# AMS_Enerdel_Adapter_rev8.net
KiCad netlist of a schematic drawn in EAGLE
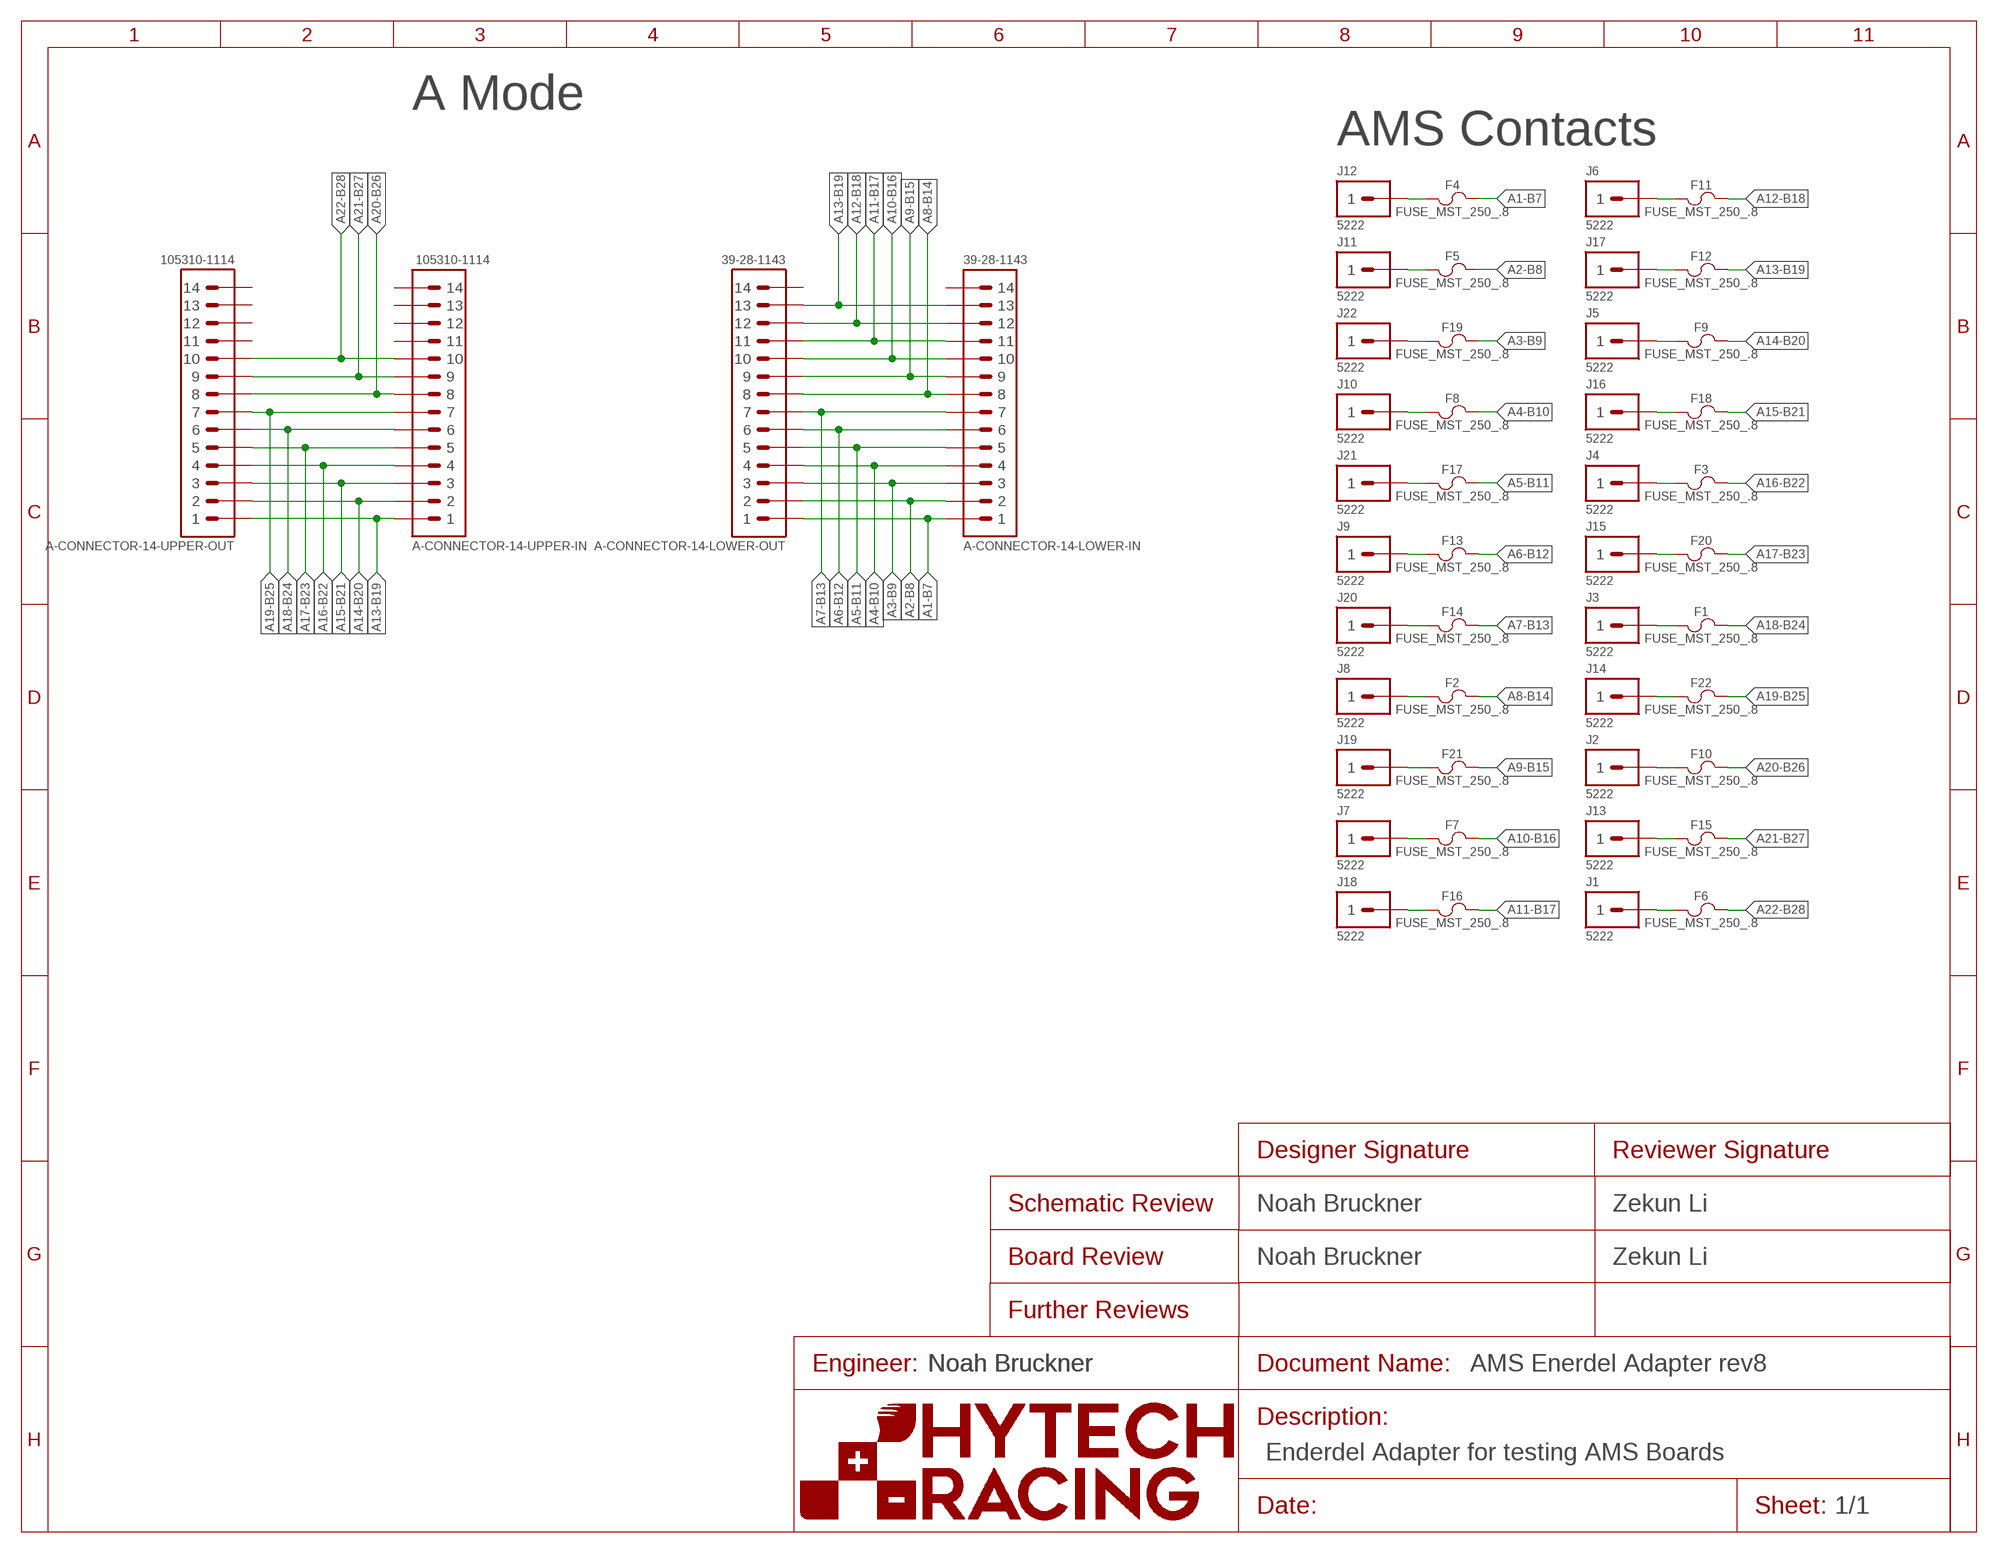
[diagram p0: schematic, sheet 1]

(export (version "E")
  (design (tool "Eeschema 10.0.6"))
  (components
    (comp (ref "A-CONNECTOR-14-LOWER-IN")
      (value "CONNECTOR-14_MINIFIT_")
      (footprint "eagle-import:MOLEX_MINIFIT_PTH_14")
      (fields (field (name "MPN") "39-28-1143"))
      (libsource (lib "eagle-import") (part "CONNECTOR-14_?_MINIFIT"))
    )
    (comp (ref "A-CONNECTOR-14-LOWER-OUT")
      (value "CONNECTOR-14_MINIFIT_")
      (footprint "eagle-import:MOLEX_MINIFIT_PTH_14")
      (fields (field (name "MPN") "39-28-1143"))
      (libsource (lib "eagle-import") (part "CONNECTOR-14_?_MINIFIT"))
    )
    (comp (ref "A-CONNECTOR-14-UPPER-IN")
      (value "CONNECTOR-14_NANOFIT_")
      (footprint "eagle-import:MOLEX_NANOFIT_PTH_14")
      (fields (field (name "MPN") " 105310-1114"))
      (libsource (lib "eagle-import") (part "CONNECTOR-14_?_NANOFIT"))
    )
    (comp (ref "A-CONNECTOR-14-UPPER-OUT")
      (value "CONNECTOR-14_NANOFIT_")
      (footprint "eagle-import:MOLEX_NANOFIT_PTH_14")
      (fields (field (name "MPN") "105310-1114"))
      (libsource (lib "eagle-import") (part "CONNECTOR-14_?_NANOFIT"))
    )
    (comp (ref "F1")
      (value "FUSE_MST_250_.8")
      (footprint "eagle-import:MST_250")
      (fields
        (field (name "MANUFACTURER") "Schurter Inc.")
        (field (name "MPN") "0034.6614")
        (field (name "VOLTAGE") "63V")
      )
      (libsource (lib "eagle-import") (part "FUSE_?_MST_250.8"))
    )
    (comp (ref "F2")
      (value "FUSE_MST_250_.8")
      (footprint "eagle-import:MST_250")
      (fields
        (field (name "MANUFACTURER") "Schurter Inc.")
        (field (name "MPN") "0034.6614")
        (field (name "VOLTAGE") "63V")
      )
      (libsource (lib "eagle-import") (part "FUSE_?_MST_250.8"))
    )
    (comp (ref "F3")
      (value "FUSE_MST_250_.8")
      (footprint "eagle-import:MST_250")
      (fields
        (field (name "MANUFACTURER") "Schurter Inc.")
        (field (name "MPN") "0034.6614")
        (field (name "VOLTAGE") "63V")
      )
      (libsource (lib "eagle-import") (part "FUSE_?_MST_250.8"))
    )
    (comp (ref "F4")
      (value "FUSE_MST_250_.8")
      (footprint "eagle-import:MST_250")
      (fields
        (field (name "MANUFACTURER") "Schurter Inc.")
        (field (name "MPN") "0034.6614")
        (field (name "VOLTAGE") "63V")
      )
      (libsource (lib "eagle-import") (part "FUSE_?_MST_250.8"))
    )
    (comp (ref "F5")
      (value "FUSE_MST_250_.8")
      (footprint "eagle-import:MST_250")
      (fields
        (field (name "MANUFACTURER") "Schurter Inc.")
        (field (name "MPN") "0034.6614")
        (field (name "VOLTAGE") "63V")
      )
      (libsource (lib "eagle-import") (part "FUSE_?_MST_250.8"))
    )
    (comp (ref "F6")
      (value "FUSE_MST_250_.8")
      (footprint "eagle-import:MST_250")
      (fields
        (field (name "MANUFACTURER") "Schurter Inc.")
        (field (name "MPN") "0034.6614")
        (field (name "VOLTAGE") "63V")
      )
      (libsource (lib "eagle-import") (part "FUSE_?_MST_250.8"))
    )
    (comp (ref "F7")
      (value "FUSE_MST_250_.8")
      (footprint "eagle-import:MST_250")
      (fields
        (field (name "MANUFACTURER") "Schurter Inc.")
        (field (name "MPN") "0034.6614")
        (field (name "VOLTAGE") "63V")
      )
      (libsource (lib "eagle-import") (part "FUSE_?_MST_250.8"))
    )
    (comp (ref "F8")
      (value "FUSE_MST_250_.8")
      (footprint "eagle-import:MST_250")
      (fields
        (field (name "MANUFACTURER") "Schurter Inc.")
        (field (name "MPN") "0034.6614")
        (field (name "VOLTAGE") "63V")
      )
      (libsource (lib "eagle-import") (part "FUSE_?_MST_250.8"))
    )
    (comp (ref "F9")
      (value "FUSE_MST_250_.8")
      (footprint "eagle-import:MST_250")
      (fields
        (field (name "MANUFACTURER") "Schurter Inc.")
        (field (name "MPN") "0034.6614")
        (field (name "VOLTAGE") "63V")
      )
      (libsource (lib "eagle-import") (part "FUSE_?_MST_250.8"))
    )
    (comp (ref "F10")
      (value "FUSE_MST_250_.8")
      (footprint "eagle-import:MST_250")
      (fields
        (field (name "MANUFACTURER") "Schurter Inc.")
        (field (name "MPN") "0034.6614")
        (field (name "VOLTAGE") "63V")
      )
      (libsource (lib "eagle-import") (part "FUSE_?_MST_250.8"))
    )
    (comp (ref "F11")
      (value "FUSE_MST_250_.8")
      (footprint "eagle-import:MST_250")
      (fields
        (field (name "MANUFACTURER") "Schurter Inc.")
        (field (name "MPN") "0034.6614")
        (field (name "VOLTAGE") "63V")
      )
      (libsource (lib "eagle-import") (part "FUSE_?_MST_250.8"))
    )
    (comp (ref "F12")
      (value "FUSE_MST_250_.8")
      (footprint "eagle-import:MST_250")
      (fields
        (field (name "MANUFACTURER") "Schurter Inc.")
        (field (name "MPN") "0034.6614")
        (field (name "VOLTAGE") "63V")
      )
      (libsource (lib "eagle-import") (part "FUSE_?_MST_250.8"))
    )
    (comp (ref "F13")
      (value "FUSE_MST_250_.8")
      (footprint "eagle-import:MST_250")
      (fields
        (field (name "MANUFACTURER") "Schurter Inc.")
        (field (name "MPN") "0034.6614")
        (field (name "VOLTAGE") "63V")
      )
      (libsource (lib "eagle-import") (part "FUSE_?_MST_250.8"))
    )
    (comp (ref "F14")
      (value "FUSE_MST_250_.8")
      (footprint "eagle-import:MST_250")
      (fields
        (field (name "MANUFACTURER") "Schurter Inc.")
        (field (name "MPN") "0034.6614")
        (field (name "VOLTAGE") "63V")
      )
      (libsource (lib "eagle-import") (part "FUSE_?_MST_250.8"))
    )
    (comp (ref "F15")
      (value "FUSE_MST_250_.8")
      (footprint "eagle-import:MST_250")
      (fields
        (field (name "MANUFACTURER") "Schurter Inc.")
        (field (name "MPN") "0034.6614")
        (field (name "VOLTAGE") "63V")
      )
      (libsource (lib "eagle-import") (part "FUSE_?_MST_250.8"))
    )
    (comp (ref "F16")
      (value "FUSE_MST_250_.8")
      (footprint "eagle-import:MST_250")
      (fields
        (field (name "MANUFACTURER") "Schurter Inc.")
        (field (name "MPN") "0034.6614")
        (field (name "VOLTAGE") "63V")
      )
      (libsource (lib "eagle-import") (part "FUSE_?_MST_250.8"))
    )
    (comp (ref "F17")
      (value "FUSE_MST_250_.8")
      (footprint "eagle-import:MST_250")
      (fields
        (field (name "MANUFACTURER") "Schurter Inc.")
        (field (name "MPN") "0034.6614")
        (field (name "VOLTAGE") "63V")
      )
      (libsource (lib "eagle-import") (part "FUSE_?_MST_250.8"))
    )
    (comp (ref "F18")
      (value "FUSE_MST_250_.8")
      (footprint "eagle-import:MST_250")
      (fields
        (field (name "MANUFACTURER") "Schurter Inc.")
        (field (name "MPN") "0034.6614")
        (field (name "VOLTAGE") "63V")
      )
      (libsource (lib "eagle-import") (part "FUSE_?_MST_250.8"))
    )
    (comp (ref "F19")
      (value "FUSE_MST_250_.8")
      (footprint "eagle-import:MST_250")
      (fields
        (field (name "MANUFACTURER") "Schurter Inc.")
        (field (name "MPN") "0034.6614")
        (field (name "VOLTAGE") "63V")
      )
      (libsource (lib "eagle-import") (part "FUSE_?_MST_250.8"))
    )
    (comp (ref "F20")
      (value "FUSE_MST_250_.8")
      (footprint "eagle-import:MST_250")
      (fields
        (field (name "MANUFACTURER") "Schurter Inc.")
        (field (name "MPN") "0034.6614")
        (field (name "VOLTAGE") "63V")
      )
      (libsource (lib "eagle-import") (part "FUSE_?_MST_250.8"))
    )
    (comp (ref "F21")
      (value "FUSE_MST_250_.8")
      (footprint "eagle-import:MST_250")
      (fields
        (field (name "MANUFACTURER") "Schurter Inc.")
        (field (name "MPN") "0034.6614")
        (field (name "VOLTAGE") "63V")
      )
      (libsource (lib "eagle-import") (part "FUSE_?_MST_250.8"))
    )
    (comp (ref "F22")
      (value "FUSE_MST_250_.8")
      (footprint "eagle-import:MST_250")
      (fields
        (field (name "MANUFACTURER") "Schurter Inc.")
        (field (name "MPN") "0034.6614")
        (field (name "VOLTAGE") "63V")
      )
      (libsource (lib "eagle-import") (part "FUSE_?_MST_250.8"))
    )
    (comp (ref "J1")
      (value "CONNECTOR-1_5222_")
      (footprint "eagle-import:5222")
      (fields (field (name "MPN") "5222") (field (name "MANUFACTURER") "Keystone Electronics"))
      (libsource (lib "eagle-import") (part "CONNECTOR-1_?_5222"))
    )
    (comp (ref "J2")
      (value "CONNECTOR-1_5222_")
      (footprint "eagle-import:5222")
      (fields (field (name "MPN") "5222") (field (name "MANUFACTURER") "Keystone Electronics"))
      (libsource (lib "eagle-import") (part "CONNECTOR-1_?_5222"))
    )
    (comp (ref "J3")
      (value "CONNECTOR-1_5222_")
      (footprint "eagle-import:5222")
      (fields (field (name "MPN") "5222") (field (name "MANUFACTURER") "Keystone Electronics"))
      (libsource (lib "eagle-import") (part "CONNECTOR-1_?_5222"))
    )
    (comp (ref "J4")
      (value "CONNECTOR-1_5222_")
      (footprint "eagle-import:5222")
      (fields (field (name "MPN") "5222") (field (name "MANUFACTURER") "Keystone Electronics"))
      (libsource (lib "eagle-import") (part "CONNECTOR-1_?_5222"))
    )
    (comp (ref "J5")
      (value "CONNECTOR-1_5222_")
      (footprint "eagle-import:5222")
      (fields (field (name "MPN") "5222") (field (name "MANUFACTURER") "Keystone Electronics"))
      (libsource (lib "eagle-import") (part "CONNECTOR-1_?_5222"))
    )
    (comp (ref "J6")
      (value "CONNECTOR-1_5222_")
      (footprint "eagle-import:5222")
      (fields (field (name "MPN") "5222") (field (name "MANUFACTURER") "Keystone Electronics"))
      (libsource (lib "eagle-import") (part "CONNECTOR-1_?_5222"))
    )
    (comp (ref "J7")
      (value "CONNECTOR-1_5222_")
      (footprint "eagle-import:5222")
      (fields (field (name "MPN") "5222") (field (name "MANUFACTURER") "Keystone Electronics"))
      (libsource (lib "eagle-import") (part "CONNECTOR-1_?_5222"))
    )
    (comp (ref "J8")
      (value "CONNECTOR-1_5222_")
      (footprint "eagle-import:5222")
      (fields (field (name "MPN") "5222") (field (name "MANUFACTURER") "Keystone Electronics"))
      (libsource (lib "eagle-import") (part "CONNECTOR-1_?_5222"))
    )
    (comp (ref "J9")
      (value "CONNECTOR-1_5222_")
      (footprint "eagle-import:5222")
      (fields (field (name "MPN") "5222") (field (name "MANUFACTURER") "Keystone Electronics"))
      (libsource (lib "eagle-import") (part "CONNECTOR-1_?_5222"))
    )
    (comp (ref "J10")
      (value "CONNECTOR-1_5222_")
      (footprint "eagle-import:5222")
      (fields (field (name "MPN") "5222") (field (name "MANUFACTURER") "Keystone Electronics"))
      (libsource (lib "eagle-import") (part "CONNECTOR-1_?_5222"))
    )
    (comp (ref "J11")
      (value "CONNECTOR-1_5222_")
      (footprint "eagle-import:5222")
      (fields (field (name "MPN") "5222") (field (name "MANUFACTURER") "Keystone Electronics"))
      (libsource (lib "eagle-import") (part "CONNECTOR-1_?_5222"))
    )
    (comp (ref "J12")
      (value "CONNECTOR-1_5222_")
      (footprint "eagle-import:5222")
      (fields (field (name "MPN") "5222") (field (name "MANUFACTURER") "Keystone Electronics"))
      (libsource (lib "eagle-import") (part "CONNECTOR-1_?_5222"))
    )
    (comp (ref "J13")
      (value "CONNECTOR-1_5222_")
      (footprint "eagle-import:5222")
      (fields (field (name "MPN") "5222") (field (name "MANUFACTURER") "Keystone Electronics"))
      (libsource (lib "eagle-import") (part "CONNECTOR-1_?_5222"))
    )
    (comp (ref "J14")
      (value "CONNECTOR-1_5222_")
      (footprint "eagle-import:5222")
      (fields (field (name "MPN") "5222") (field (name "MANUFACTURER") "Keystone Electronics"))
      (libsource (lib "eagle-import") (part "CONNECTOR-1_?_5222"))
    )
    (comp (ref "J15")
      (value "CONNECTOR-1_5222_")
      (footprint "eagle-import:5222")
      (fields (field (name "MPN") "5222") (field (name "MANUFACTURER") "Keystone Electronics"))
      (libsource (lib "eagle-import") (part "CONNECTOR-1_?_5222"))
    )
    (comp (ref "J16")
      (value "CONNECTOR-1_5222_")
      (footprint "eagle-import:5222")
      (fields (field (name "MPN") "5222") (field (name "MANUFACTURER") "Keystone Electronics"))
      (libsource (lib "eagle-import") (part "CONNECTOR-1_?_5222"))
    )
    (comp (ref "J17")
      (value "CONNECTOR-1_5222_")
      (footprint "eagle-import:5222")
      (fields (field (name "MPN") "5222") (field (name "MANUFACTURER") "Keystone Electronics"))
      (libsource (lib "eagle-import") (part "CONNECTOR-1_?_5222"))
    )
    (comp (ref "J18")
      (value "CONNECTOR-1_5222_")
      (footprint "eagle-import:5222")
      (fields (field (name "MPN") "5222") (field (name "MANUFACTURER") "Keystone Electronics"))
      (libsource (lib "eagle-import") (part "CONNECTOR-1_?_5222"))
    )
    (comp (ref "J19")
      (value "CONNECTOR-1_5222_")
      (footprint "eagle-import:5222")
      (fields (field (name "MPN") "5222") (field (name "MANUFACTURER") "Keystone Electronics"))
      (libsource (lib "eagle-import") (part "CONNECTOR-1_?_5222"))
    )
    (comp (ref "J20")
      (value "CONNECTOR-1_5222_")
      (footprint "eagle-import:5222")
      (fields (field (name "MPN") "5222") (field (name "MANUFACTURER") "Keystone Electronics"))
      (libsource (lib "eagle-import") (part "CONNECTOR-1_?_5222"))
    )
    (comp (ref "J21")
      (value "CONNECTOR-1_5222_")
      (footprint "eagle-import:5222")
      (fields (field (name "MPN") "5222") (field (name "MANUFACTURER") "Keystone Electronics"))
      (libsource (lib "eagle-import") (part "CONNECTOR-1_?_5222"))
    )
    (comp (ref "J22")
      (value "CONNECTOR-1_5222_")
      (footprint "eagle-import:5222")
      (fields (field (name "MPN") "5222") (field (name "MANUFACTURER") "Keystone Electronics"))
      (libsource (lib "eagle-import") (part "CONNECTOR-1_?_5222"))
    )
  )
  (nets
    (net (code "1") (name "A1-B7") (class "Default")
      (node (ref "A-CONNECTOR-14-LOWER-IN") (pin "1") (pinfunction "1_1") (pintype "passive"))
      (node (ref "A-CONNECTOR-14-LOWER-OUT") (pin "1") (pinfunction "1_1") (pintype "passive"))
      (node (ref "F4") (pin "2") (pinfunction "2_2") (pintype "passive"))
    )
    (net (code "2") (name "A2-B8") (class "Default")
      (node (ref "A-CONNECTOR-14-LOWER-IN") (pin "2") (pinfunction "2_2") (pintype "passive"))
      (node (ref "A-CONNECTOR-14-LOWER-OUT") (pin "2") (pinfunction "2_2") (pintype "passive"))
      (node (ref "F5") (pin "2") (pinfunction "2_2") (pintype "passive"))
    )
    (net (code "3") (name "A3-B9") (class "Default")
      (node (ref "A-CONNECTOR-14-LOWER-IN") (pin "3") (pinfunction "3_3") (pintype "passive"))
      (node (ref "A-CONNECTOR-14-LOWER-OUT") (pin "3") (pinfunction "3_3") (pintype "passive"))
      (node (ref "F19") (pin "2") (pinfunction "2_2") (pintype "passive"))
    )
    (net (code "4") (name "A4-B10") (class "Default")
      (node (ref "A-CONNECTOR-14-LOWER-IN") (pin "4") (pinfunction "4_4") (pintype "passive"))
      (node (ref "A-CONNECTOR-14-LOWER-OUT") (pin "4") (pinfunction "4_4") (pintype "passive"))
      (node (ref "F8") (pin "2") (pinfunction "2_2") (pintype "passive"))
    )
    (net (code "5") (name "A5-B11") (class "Default")
      (node (ref "A-CONNECTOR-14-LOWER-IN") (pin "5") (pinfunction "5_5") (pintype "passive"))
      (node (ref "A-CONNECTOR-14-LOWER-OUT") (pin "5") (pinfunction "5_5") (pintype "passive"))
      (node (ref "F17") (pin "2") (pinfunction "2_2") (pintype "passive"))
    )
    (net (code "6") (name "A6-B12") (class "Default")
      (node (ref "A-CONNECTOR-14-LOWER-IN") (pin "6") (pinfunction "6_6") (pintype "passive"))
      (node (ref "A-CONNECTOR-14-LOWER-OUT") (pin "6") (pinfunction "6_6") (pintype "passive"))
      (node (ref "F13") (pin "2") (pinfunction "2_2") (pintype "passive"))
    )
    (net (code "7") (name "A7-B13") (class "Default")
      (node (ref "A-CONNECTOR-14-LOWER-IN") (pin "7") (pinfunction "7_7") (pintype "passive"))
      (node (ref "A-CONNECTOR-14-LOWER-OUT") (pin "7") (pinfunction "7_7") (pintype "passive"))
      (node (ref "F14") (pin "2") (pinfunction "2_2") (pintype "passive"))
    )
    (net (code "8") (name "A8-B14") (class "Default")
      (node (ref "A-CONNECTOR-14-LOWER-IN") (pin "8") (pinfunction "8_8") (pintype "passive"))
      (node (ref "A-CONNECTOR-14-LOWER-OUT") (pin "8") (pinfunction "8_8") (pintype "passive"))
      (node (ref "F2") (pin "2") (pinfunction "2_2") (pintype "passive"))
    )
    (net (code "9") (name "A9-B15") (class "Default")
      (node (ref "A-CONNECTOR-14-LOWER-IN") (pin "9") (pinfunction "9_9") (pintype "passive"))
      (node (ref "A-CONNECTOR-14-LOWER-OUT") (pin "9") (pinfunction "9_9") (pintype "passive"))
      (node (ref "F21") (pin "2") (pinfunction "2_2") (pintype "passive"))
    )
    (net (code "10") (name "A10-B16") (class "Default")
      (node (ref "A-CONNECTOR-14-LOWER-IN") (pin "10") (pinfunction "10_10") (pintype "passive"))
      (node (ref "A-CONNECTOR-14-LOWER-OUT") (pin "10") (pinfunction "10_10") (pintype "passive"))
      (node (ref "F7") (pin "2") (pinfunction "2_2") (pintype "passive"))
    )
    (net (code "11") (name "A11-B17") (class "Default")
      (node (ref "A-CONNECTOR-14-LOWER-IN") (pin "11") (pinfunction "11_11") (pintype "passive"))
      (node (ref "A-CONNECTOR-14-LOWER-OUT") (pin "11") (pinfunction "11_11") (pintype "passive"))
      (node (ref "F16") (pin "2") (pinfunction "2_2") (pintype "passive"))
    )
    (net (code "12") (name "A12-B18") (class "Default")
      (node (ref "A-CONNECTOR-14-LOWER-IN") (pin "12") (pinfunction "12_12") (pintype "passive"))
      (node (ref "A-CONNECTOR-14-LOWER-OUT") (pin "12") (pinfunction "12_12") (pintype "passive"))
      (node (ref "F11") (pin "2") (pinfunction "2_2") (pintype "passive"))
    )
    (net (code "13") (name "A13-B19") (class "Default")
      (node (ref "A-CONNECTOR-14-LOWER-IN") (pin "13") (pinfunction "13_13") (pintype "passive"))
      (node (ref "A-CONNECTOR-14-LOWER-OUT") (pin "13") (pinfunction "13_13") (pintype "passive"))
      (node (ref "A-CONNECTOR-14-UPPER-IN") (pin "1") (pinfunction "1_1") (pintype "passive"))
      (node (ref "A-CONNECTOR-14-UPPER-OUT") (pin "1") (pinfunction "1_1") (pintype "passive"))
      (node (ref "F12") (pin "2") (pinfunction "2_2") (pintype "passive"))
    )
    (net (code "14") (name "A14-B20") (class "Default")
      (node (ref "A-CONNECTOR-14-UPPER-IN") (pin "2") (pinfunction "2_2") (pintype "passive"))
      (node (ref "A-CONNECTOR-14-UPPER-OUT") (pin "2") (pinfunction "2_2") (pintype "passive"))
      (node (ref "F9") (pin "2") (pinfunction "2_2") (pintype "passive"))
    )
    (net (code "15") (name "A15-B21") (class "Default")
      (node (ref "A-CONNECTOR-14-UPPER-IN") (pin "3") (pinfunction "3_3") (pintype "passive"))
      (node (ref "A-CONNECTOR-14-UPPER-OUT") (pin "3") (pinfunction "3_3") (pintype "passive"))
      (node (ref "F18") (pin "2") (pinfunction "2_2") (pintype "passive"))
    )
    (net (code "16") (name "A16-B22") (class "Default")
      (node (ref "A-CONNECTOR-14-UPPER-IN") (pin "4") (pinfunction "4_4") (pintype "passive"))
      (node (ref "A-CONNECTOR-14-UPPER-OUT") (pin "4") (pinfunction "4_4") (pintype "passive"))
      (node (ref "F3") (pin "2") (pinfunction "2_2") (pintype "passive"))
    )
    (net (code "17") (name "A17-B23") (class "Default")
      (node (ref "A-CONNECTOR-14-UPPER-IN") (pin "5") (pinfunction "5_5") (pintype "passive"))
      (node (ref "A-CONNECTOR-14-UPPER-OUT") (pin "5") (pinfunction "5_5") (pintype "passive"))
      (node (ref "F20") (pin "2") (pinfunction "2_2") (pintype "passive"))
    )
    (net (code "18") (name "A18-B24") (class "Default")
      (node (ref "A-CONNECTOR-14-UPPER-IN") (pin "6") (pinfunction "6_6") (pintype "passive"))
      (node (ref "A-CONNECTOR-14-UPPER-OUT") (pin "6") (pinfunction "6_6") (pintype "passive"))
      (node (ref "F1") (pin "2") (pinfunction "2_2") (pintype "passive"))
    )
    (net (code "19") (name "A19-B25") (class "Default")
      (node (ref "A-CONNECTOR-14-UPPER-IN") (pin "7") (pinfunction "7_7") (pintype "passive"))
      (node (ref "A-CONNECTOR-14-UPPER-OUT") (pin "7") (pinfunction "7_7") (pintype "passive"))
      (node (ref "F22") (pin "2") (pinfunction "2_2") (pintype "passive"))
    )
    (net (code "20") (name "A20-B26") (class "Default")
      (node (ref "A-CONNECTOR-14-UPPER-IN") (pin "8") (pinfunction "8_8") (pintype "passive"))
      (node (ref "A-CONNECTOR-14-UPPER-OUT") (pin "8") (pinfunction "8_8") (pintype "passive"))
      (node (ref "F10") (pin "2") (pinfunction "2_2") (pintype "passive"))
    )
    (net (code "21") (name "A21-B27") (class "Default")
      (node (ref "A-CONNECTOR-14-UPPER-IN") (pin "9") (pinfunction "9_9") (pintype "passive"))
      (node (ref "A-CONNECTOR-14-UPPER-OUT") (pin "9") (pinfunction "9_9") (pintype "passive"))
      (node (ref "F15") (pin "2") (pinfunction "2_2") (pintype "passive"))
    )
    (net (code "22") (name "A22-B28") (class "Default")
      (node (ref "A-CONNECTOR-14-UPPER-IN") (pin "10") (pinfunction "10_10") (pintype "passive"))
      (node (ref "A-CONNECTOR-14-UPPER-OUT") (pin "10") (pinfunction "10_10") (pintype "passive"))
      (node (ref "F6") (pin "2") (pinfunction "2_2") (pintype "passive"))
    )
    (net (code "23") (name "Net-(F1-Pad1)") (class "Default")
      (node (ref "F1") (pin "1") (pinfunction "1_1") (pintype "passive"))
      (node (ref "J3") (pin "1") (pinfunction "1_1") (pintype "passive"))
    )
    (net (code "24") (name "Net-(F2-Pad1)") (class "Default")
      (node (ref "F2") (pin "1") (pinfunction "1_1") (pintype "passive"))
      (node (ref "J8") (pin "1") (pinfunction "1_1") (pintype "passive"))
    )
    (net (code "25") (name "Net-(F3-Pad1)") (class "Default")
      (node (ref "F3") (pin "1") (pinfunction "1_1") (pintype "passive"))
      (node (ref "J4") (pin "1") (pinfunction "1_1") (pintype "passive"))
    )
    (net (code "26") (name "Net-(F4-Pad1)") (class "Default")
      (node (ref "F4") (pin "1") (pinfunction "1_1") (pintype "passive"))
      (node (ref "J12") (pin "1") (pinfunction "1_1") (pintype "passive"))
    )
    (net (code "27") (name "Net-(F5-Pad1)") (class "Default")
      (node (ref "F5") (pin "1") (pinfunction "1_1") (pintype "passive"))
      (node (ref "J11") (pin "1") (pinfunction "1_1") (pintype "passive"))
    )
    (net (code "28") (name "Net-(F6-Pad1)") (class "Default")
      (node (ref "F6") (pin "1") (pinfunction "1_1") (pintype "passive"))
      (node (ref "J1") (pin "1") (pinfunction "1_1") (pintype "passive"))
    )
    (net (code "29") (name "Net-(F7-Pad1)") (class "Default")
      (node (ref "F7") (pin "1") (pinfunction "1_1") (pintype "passive"))
      (node (ref "J7") (pin "1") (pinfunction "1_1") (pintype "passive"))
    )
    (net (code "30") (name "Net-(F8-Pad1)") (class "Default")
      (node (ref "F8") (pin "1") (pinfunction "1_1") (pintype "passive"))
      (node (ref "J10") (pin "1") (pinfunction "1_1") (pintype "passive"))
    )
    (net (code "31") (name "Net-(F9-Pad1)") (class "Default")
      (node (ref "F9") (pin "1") (pinfunction "1_1") (pintype "passive"))
      (node (ref "J5") (pin "1") (pinfunction "1_1") (pintype "passive"))
    )
    (net (code "32") (name "Net-(F10-Pad1)") (class "Default")
      (node (ref "F10") (pin "1") (pinfunction "1_1") (pintype "passive"))
      (node (ref "J2") (pin "1") (pinfunction "1_1") (pintype "passive"))
    )
    (net (code "33") (name "Net-(F11-Pad1)") (class "Default")
      (node (ref "F11") (pin "1") (pinfunction "1_1") (pintype "passive"))
      (node (ref "J6") (pin "1") (pinfunction "1_1") (pintype "passive"))
    )
    (net (code "34") (name "Net-(F12-Pad1)") (class "Default")
      (node (ref "F12") (pin "1") (pinfunction "1_1") (pintype "passive"))
      (node (ref "J17") (pin "1") (pinfunction "1_1") (pintype "passive"))
    )
    (net (code "35") (name "Net-(F13-Pad1)") (class "Default")
      (node (ref "F13") (pin "1") (pinfunction "1_1") (pintype "passive"))
      (node (ref "J9") (pin "1") (pinfunction "1_1") (pintype "passive"))
    )
    (net (code "36") (name "Net-(F14-Pad1)") (class "Default")
      (node (ref "F14") (pin "1") (pinfunction "1_1") (pintype "passive"))
      (node (ref "J20") (pin "1") (pinfunction "1_1") (pintype "passive"))
    )
    (net (code "37") (name "Net-(F15-Pad1)") (class "Default")
      (node (ref "F15") (pin "1") (pinfunction "1_1") (pintype "passive"))
      (node (ref "J13") (pin "1") (pinfunction "1_1") (pintype "passive"))
    )
    (net (code "38") (name "Net-(F16-Pad1)") (class "Default")
      (node (ref "F16") (pin "1") (pinfunction "1_1") (pintype "passive"))
      (node (ref "J18") (pin "1") (pinfunction "1_1") (pintype "passive"))
    )
    (net (code "39") (name "Net-(F17-Pad1)") (class "Default")
      (node (ref "F17") (pin "1") (pinfunction "1_1") (pintype "passive"))
      (node (ref "J21") (pin "1") (pinfunction "1_1") (pintype "passive"))
    )
    (net (code "40") (name "Net-(F18-Pad1)") (class "Default")
      (node (ref "F18") (pin "1") (pinfunction "1_1") (pintype "passive"))
      (node (ref "J16") (pin "1") (pinfunction "1_1") (pintype "passive"))
    )
    (net (code "41") (name "Net-(F19-Pad1)") (class "Default")
      (node (ref "F19") (pin "1") (pinfunction "1_1") (pintype "passive"))
      (node (ref "J22") (pin "1") (pinfunction "1_1") (pintype "passive"))
    )
    (net (code "42") (name "Net-(F20-Pad1)") (class "Default")
      (node (ref "F20") (pin "1") (pinfunction "1_1") (pintype "passive"))
      (node (ref "J15") (pin "1") (pinfunction "1_1") (pintype "passive"))
    )
    (net (code "43") (name "Net-(F21-Pad1)") (class "Default")
      (node (ref "F21") (pin "1") (pinfunction "1_1") (pintype "passive"))
      (node (ref "J19") (pin "1") (pinfunction "1_1") (pintype "passive"))
    )
    (net (code "44") (name "Net-(F22-Pad1)") (class "Default")
      (node (ref "F22") (pin "1") (pinfunction "1_1") (pintype "passive"))
      (node (ref "J14") (pin "1") (pinfunction "1_1") (pintype "passive"))
    )
    (net (code "45") (name "unconnected-(A-CONNECTOR-14-LOWER-IN-Pad14)") (class "Default")
      (node (ref "A-CONNECTOR-14-LOWER-IN") (pin "14") (pinfunction "14_14") (pintype "passive"))
    )
    (net (code "46") (name "unconnected-(A-CONNECTOR-14-LOWER-OUT-Pad14)") (class "Default")
      (node (ref "A-CONNECTOR-14-LOWER-OUT") (pin "14") (pinfunction "14_14") (pintype "passive"))
    )
    (net (code "47") (name "unconnected-(A-CONNECTOR-14-UPPER-IN-Pad11)") (class "Default")
      (node (ref "A-CONNECTOR-14-UPPER-IN") (pin "11") (pinfunction "11_11") (pintype "passive"))
    )
    (net (code "48") (name "unconnected-(A-CONNECTOR-14-UPPER-IN-Pad12)") (class "Default")
      (node (ref "A-CONNECTOR-14-UPPER-IN") (pin "12") (pinfunction "12_12") (pintype "passive"))
    )
    (net (code "49") (name "unconnected-(A-CONNECTOR-14-UPPER-IN-Pad13)") (class "Default")
      (node (ref "A-CONNECTOR-14-UPPER-IN") (pin "13") (pinfunction "13_13") (pintype "passive"))
    )
    (net (code "50") (name "unconnected-(A-CONNECTOR-14-UPPER-IN-Pad14)") (class "Default")
      (node (ref "A-CONNECTOR-14-UPPER-IN") (pin "14") (pinfunction "14_14") (pintype "passive"))
    )
    (net (code "51") (name "unconnected-(A-CONNECTOR-14-UPPER-OUT-Pad11)") (class "Default")
      (node (ref "A-CONNECTOR-14-UPPER-OUT") (pin "11") (pinfunction "11_11") (pintype "passive"))
    )
    (net (code "52") (name "unconnected-(A-CONNECTOR-14-UPPER-OUT-Pad12)") (class "Default")
      (node (ref "A-CONNECTOR-14-UPPER-OUT") (pin "12") (pinfunction "12_12") (pintype "passive"))
    )
    (net (code "53") (name "unconnected-(A-CONNECTOR-14-UPPER-OUT-Pad13)") (class "Default")
      (node (ref "A-CONNECTOR-14-UPPER-OUT") (pin "13") (pinfunction "13_13") (pintype "passive"))
    )
    (net (code "54") (name "unconnected-(A-CONNECTOR-14-UPPER-OUT-Pad14)") (class "Default")
      (node (ref "A-CONNECTOR-14-UPPER-OUT") (pin "14") (pinfunction "14_14") (pintype "passive"))
    )
  )
)
